# Power.net
KiCad netlist of a schematic drawn in Altium Designer
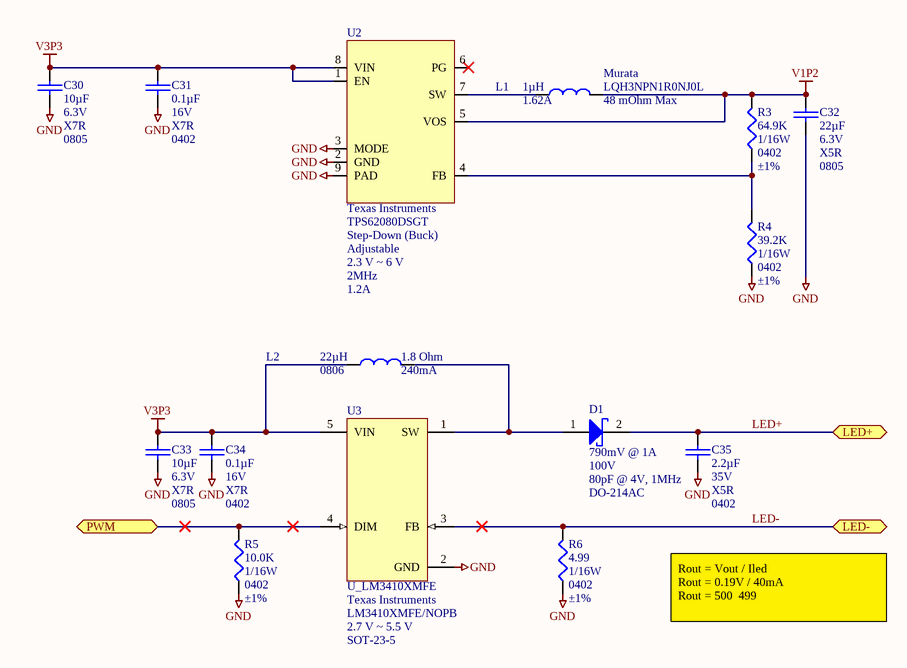
[diagram p0: Power.SchDoc]

(export (version "E")
  (design (tool "Eeschema 10.0.6"))
  (components
    (comp (ref "C30")
      (value "10uF")
      (footprint "C_ERA-0805")
      (description "CAP CER 10UF 6.3V X7R 10% 0805")
      (fields
        (field (name "MANUFACTURER") "Taiyo Yuden")
        (field (name "MANUFACTURER PART NUMBER") "JMK212BJ106KD-T")
        (field (name "CAPACITANCE") "10µF")
        (field (name "VOLTAGE - RATED") "6.3V")
        (field (name "TEMPERATURE COEFFICIENT") "X7R")
        (field (name "PACKAGE / CASE") "0805")
      )
      (libsource (lib "Main LibraryX") (part "C_0805_10UF_6.3V"))
    )
    (comp (ref "C31")
      (value "0.1uF")
      (footprint "C_ERA-0402")
      (description "CAP CER .10UF 16V X7R 0402")
      (fields
        (field (name "MANUFACTURER") "TDK Corporation")
        (field (name "MANUFACTURER PART NUMBER") "C1005X7R1C104K")
        (field (name "CAPACITANCE") "0.1µF")
        (field (name "VOLTAGE - RATED") "16V")
        (field (name "TEMPERATURE COEFFICIENT") "X7R")
        (field (name "PACKAGE / CASE") "0402")
      )
      (libsource (lib "Main LibraryX") (part "C_0402_0.1UF_16V"))
    )
    (comp (ref "C32")
      (value "22uF")
      (footprint "C_ERA-0805")
      (description "CAP CER 22UF 6.3V X7R 10% 0805")
      (fields
        (field (name "MANUFACTURER") "AVX Corporation")
        (field (name "MANUFACTURER PART NUMBER") "08056D226MAT2A")
        (field (name "CAPACITANCE") "22µF")
        (field (name "VOLTAGE - RATED") "6.3V")
        (field (name "TEMPERATURE COEFFICIENT") "X5R")
        (field (name "PACKAGE / CASE") "0805")
      )
      (libsource (lib "Main LibraryX") (part "C_0805_22UF_6.3V"))
    )
    (comp (ref "C33")
      (value "10uF")
      (footprint "C_ERA-0805")
      (description "CAP CER 10UF 6.3V X7R 10% 0805")
      (fields
        (field (name "MANUFACTURER") "Taiyo Yuden")
        (field (name "MANUFACTURER PART NUMBER") "JMK212BJ106KD-T")
        (field (name "CAPACITANCE") "10µF")
        (field (name "VOLTAGE - RATED") "6.3V")
        (field (name "TEMPERATURE COEFFICIENT") "X7R")
        (field (name "PACKAGE / CASE") "0805")
      )
      (libsource (lib "Main LibraryX") (part "C_0805_10UF_6.3V"))
    )
    (comp (ref "C34")
      (value "0.1uF")
      (footprint "C_ERA-0402")
      (description "CAP CER .10UF 16V X7R 0402")
      (fields
        (field (name "MANUFACTURER") "TDK Corporation")
        (field (name "MANUFACTURER PART NUMBER") "C1005X7R1C104K")
        (field (name "CAPACITANCE") "0.1µF")
        (field (name "VOLTAGE - RATED") "16V")
        (field (name "TEMPERATURE COEFFICIENT") "X7R")
        (field (name "PACKAGE / CASE") "0402")
      )
      (libsource (lib "Main LibraryX") (part "C_0402_0.1UF_16V"))
    )
    (comp (ref "C35")
      (value "C_0402_2.2uF_35V")
      (footprint "C_ERA-0402")
      (description "CAP CER 2.2UF 35V 20% X5R 0402")
      (fields
        (field (name "CAPACITANCE") "2.2µF")
        (field (name "VOLTAGE - RATED") "35V")
        (field (name "TEMPERATURE COEFFICIENT") "X5R")
        (field (name "PACKAGE / CASE") "0402")
        (field (name "MANUFACTURER") "TDK Corporation")
        (field (name "MANUFACTURER PART NUMBER") "C1005X5R1V225M050BC")
      )
      (libsource (lib "Main LibraryX") (part "C_0402_2.2uF_35V"))
    )
    (comp (ref "D1")
      (value "B1100-13-F")
      (footprint "DIOM5226X23L")
      (description "DIODE SCHOTTKY 100V 1A SMA")
      (fields
        (field (name "MANUFACTURER") "Diodes Inc")
        (field (name "VOLTAGE - FORWARD (VF) (MAX) @ IF") "790mV @ 1A")
        (field (name "VOLTAGE - DC REVERSE (VR) (MAX)") "100V")
        (field (name "CAPACITANCE @ VR, F") "80pF @ 4V, 1MHz")
        (field (name "PACKAGE / CASE") "DO-214AC")
      )
      (libsource (lib "Main Library") (part "D_SCHOTT_B1100-13-F"))
    )
    (comp (ref "L1")
      (value "1.0uH")
      (footprint "INDNRH1212")
      (description "INDUCTOR POWER 1.0UH 1620MA 1212")
      (fields
        (field (name "TOLERANCE") "±30%")
        (field (name "MANUFACTURER PART NUMBER") "LQH3NPN1R0NJ0L")
        (field (name "INDUCTANCE") "1µH")
        (field (name "CURRENT") "1.62A")
        (field (name "DC RESISTANCE (DCR)") "48 mOhm Max")
        (field (name "MANUFACTURER") "Murata")
      )
      (libsource (lib "Main Library") (part "L_1.0UH_1.62A"))
    )
    (comp (ref "L2")
      (value "CBC2016T220K")
      (footprint "L_0806")
      (description "INDUCTOR 22UH 10% 0806 SMD")
      (fields
        (field (name "MANUFACTURER") "Taiyo Yuden")
        (field (name "TOLERANCE") "±10%")
        (field (name "CURRENT") "240mA")
        (field (name "PACKAGE / CASE") "0806")
        (field (name "INDUCTANCE") "22µH")
        (field (name "DC RESISTANCE (DCR)") "1.8 Ohm")
      )
      (libsource (lib "Main Library") (part "L_0806_22uH"))
    )
    (comp (ref "R3")
      (value "R_0402_64.9K")
      (footprint "ERA-0402")
      (description "RES 64.9K OHM 1/16W 1% 0402 SMD")
      (fields
        (field (name "MANUFACTURER") "Yageo")
        (field (name "MANUFACTURER PART NUMBER") "RC0402FR-0764K9L")
        (field (name "RESISTANCE IN OHMS") "64.9K")
        (field (name "POWER (WATTS)") "1/16W")
        (field (name "CASE") "0402")
        (field (name "TOLERANCE") "±1%")
      )
      (libsource (lib "Main Library") (part "R_0402_64.9K"))
    )
    (comp (ref "R4")
      (value "R_0402_39.2K")
      (footprint "ERA-0402")
      (description "RES 39.2K OHM 1/16W 1% 0402 SMD")
      (fields
        (field (name "RESISTANCE IN OHMS") "39.2K")
        (field (name "POWER (WATTS)") "1/16W")
        (field (name "CASE") "0402")
        (field (name "TOLERANCE") "±1%")
        (field (name "MANUFACTURER") "Yageo")
        (field (name "MANUFACTURER PART NUMBER") "RC0402FR-0739K2L")
      )
      (libsource (lib "Main LibraryX") (part "R_0402_39.2K"))
    )
    (comp (ref "R5")
      (value "R_0402_10.0K")
      (footprint "R_0402")
      (description "RES 10.0K OHM 1/16W 1% 0402 SMD")
      (fields
        (field (name "MANUFACTURER") "Stackpole Electronics Inc")
        (field (name "MANUFACTURER PART NUMBER") "RMCF0402FT10K0")
        (field (name "RESISTANCE IN OHMS") "10.0K")
        (field (name "POWER (WATTS)") "1/16W")
        (field (name "CASE") "0402")
        (field (name "TOLERANCE") "±1%")
      )
      (libsource (lib "Main Library") (part "R_0402_10.0K"))
    )
    (comp (ref "R6")
      (value "R_0402_4.99")
      (footprint "R_0402")
      (description "RES 4.99 OHM 1/16W 1% 0402")
      (fields
        (field (name "MANUFACTURER") "Stackpole Electronics Inc")
        (field (name "MANUFACTURER PART NUMBER") "RMCF0402FT4R99")
        (field (name "RESISTANCE IN OHMS") "4.99")
        (field (name "POWER (WATTS)") "1/16W")
        (field (name "CASE") "0402")
        (field (name "TOLERANCE") "±1%")
      )
      (libsource (lib "Main Library") (part "R_0402_4.99"))
    )
    (comp (ref "U2")
      (value "TPS62080")
      (footprint "QFN50P200X200X80-8L")
      (description "IC BUCK SYNC ADJ 1.2A 8WSON")
      (fields
        (field (name "MANUFACTURER") "Texas Instruments")
        (field (name "MANUFACTURER PART NUMBER") "TPS62080DSGT")
        (field (name "TYPE") "Step-Down (Buck)")
        (field (name "OUTPUT TYPE") "Adjustable")
        (field (name "VOLTAGE - INPUT") "2.3 V ~ 6 V")
        (field (name "FREQUENCY - SWITCHING") "2MHz")
        (field (name "CURRENT - OUTPUT") "1.2A")
      )
      (libsource (lib "Main Library") (part "U_TPS62080"))
    )
    (comp (ref "U3")
      (value "U_LM3410XMFE")
      (footprint "MF05A_N")
      (description "IC DRVR WT/OLED BCKLT SOT23-5")
      (fields
        (field (name "MANUFACTURER") "Texas Instruments")
        (field (name "MANUFACTURER PART NUMBER") "LM3410XMFE/NOPB")
        (field (name "VOLTAGE - SUPPLY") "2.7 V ~ 5.5 V")
        (field (name "SUPPLIER DEVICE PACKAGE") "SOT-23-5")
      )
      (libsource (lib "Main Library") (part "U_LM3410XMFE"))
    )
  )
  (nets
    (net (code "1") (name "/LED+") (class "Default")
      (node (ref "C35") (pin "2") (pinfunction "2_2") (pintype "passive"))
      (node (ref "D1") (pin "2") (pinfunction "K_2") (pintype "passive"))
    )
    (net (code "2") (name "/LED-") (class "Default")
      (node (ref "R6") (pin "1") (pinfunction "1_1") (pintype "passive"))
      (node (ref "U3") (pin "3") (pinfunction "FB_3") (pintype "input"))
    )
    (net (code "3") (name "/PWM") (class "Default")
      (node (ref "R5") (pin "1") (pinfunction "1_1") (pintype "passive"))
      (node (ref "U3") (pin "4") (pinfunction "DIM_4") (pintype "input"))
    )
    (net (code "4") (name "GND") (class "Default")
      (node (ref "C30") (pin "1") (pinfunction "1_1") (pintype "passive"))
      (node (ref "C31") (pin "1") (pinfunction "1_1") (pintype "passive"))
      (node (ref "C32") (pin "1") (pinfunction "1_1") (pintype "passive"))
      (node (ref "C33") (pin "1") (pinfunction "1_1") (pintype "passive"))
      (node (ref "C34") (pin "1") (pinfunction "1_1") (pintype "passive"))
      (node (ref "C35") (pin "1") (pinfunction "1_1") (pintype "passive"))
      (node (ref "R4") (pin "2") (pinfunction "2_2") (pintype "passive"))
      (node (ref "R5") (pin "2") (pinfunction "2_2") (pintype "passive"))
      (node (ref "R6") (pin "2") (pinfunction "2_2") (pintype "passive"))
      (node (ref "U2") (pin "2") (pinfunction "GND_2") (pintype "passive"))
      (node (ref "U2") (pin "3") (pinfunction "MODE_3") (pintype "passive"))
      (node (ref "U2") (pin "9") (pinfunction "PAD_9") (pintype "passive"))
      (node (ref "U3") (pin "2") (pinfunction "GND_2") (pintype "power_in"))
    )
    (net (code "5") (name "Net-(D1-A)") (class "Default")
      (node (ref "D1") (pin "1") (pinfunction "A_1") (pintype "passive"))
      (node (ref "L2") (pin "2") (pintype "passive"))
      (node (ref "U3") (pin "1") (pinfunction "SW_1") (pintype "power_in"))
    )
    (net (code "6") (name "Net-(U2-FB)") (class "Default")
      (node (ref "R3") (pin "2") (pinfunction "2_2") (pintype "passive"))
      (node (ref "R4") (pin "1") (pinfunction "1_1") (pintype "passive"))
      (node (ref "U2") (pin "4") (pinfunction "FB_4") (pintype "passive"))
    )
    (net (code "7") (name "Net-(U2-SW)") (class "Default")
      (node (ref "L1") (pin "1") (pintype "passive"))
      (node (ref "U2") (pin "7") (pinfunction "SW_7") (pintype "passive"))
    )
    (net (code "8") (name "V1P2") (class "Default")
      (node (ref "C32") (pin "2") (pinfunction "2_2") (pintype "passive"))
      (node (ref "L1") (pin "2") (pintype "passive"))
      (node (ref "R3") (pin "1") (pinfunction "1_1") (pintype "passive"))
      (node (ref "U2") (pin "5") (pinfunction "VOS_5") (pintype "passive"))
    )
    (net (code "9") (name "V3P3") (class "Default")
      (node (ref "C30") (pin "2") (pinfunction "2_2") (pintype "passive"))
      (node (ref "C31") (pin "2") (pinfunction "2_2") (pintype "passive"))
      (node (ref "C33") (pin "2") (pinfunction "2_2") (pintype "passive"))
      (node (ref "C34") (pin "2") (pinfunction "2_2") (pintype "passive"))
      (node (ref "L2") (pin "1") (pintype "passive"))
      (node (ref "U2") (pin "1") (pinfunction "EN_1") (pintype "passive"))
      (node (ref "U2") (pin "8") (pinfunction "VIN_8") (pintype "passive"))
      (node (ref "U3") (pin "5") (pinfunction "VIN_5") (pintype "power_in"))
    )
    (net (code "10") (name "unconnected-(U2-PG-Pad6)") (class "Default")
      (node (ref "U2") (pin "6") (pinfunction "PG_6") (pintype "passive+no_connect"))
    )
  )
)
